# LogiGSM.net
KiCad netlist of a schematic drawn in EAGLE
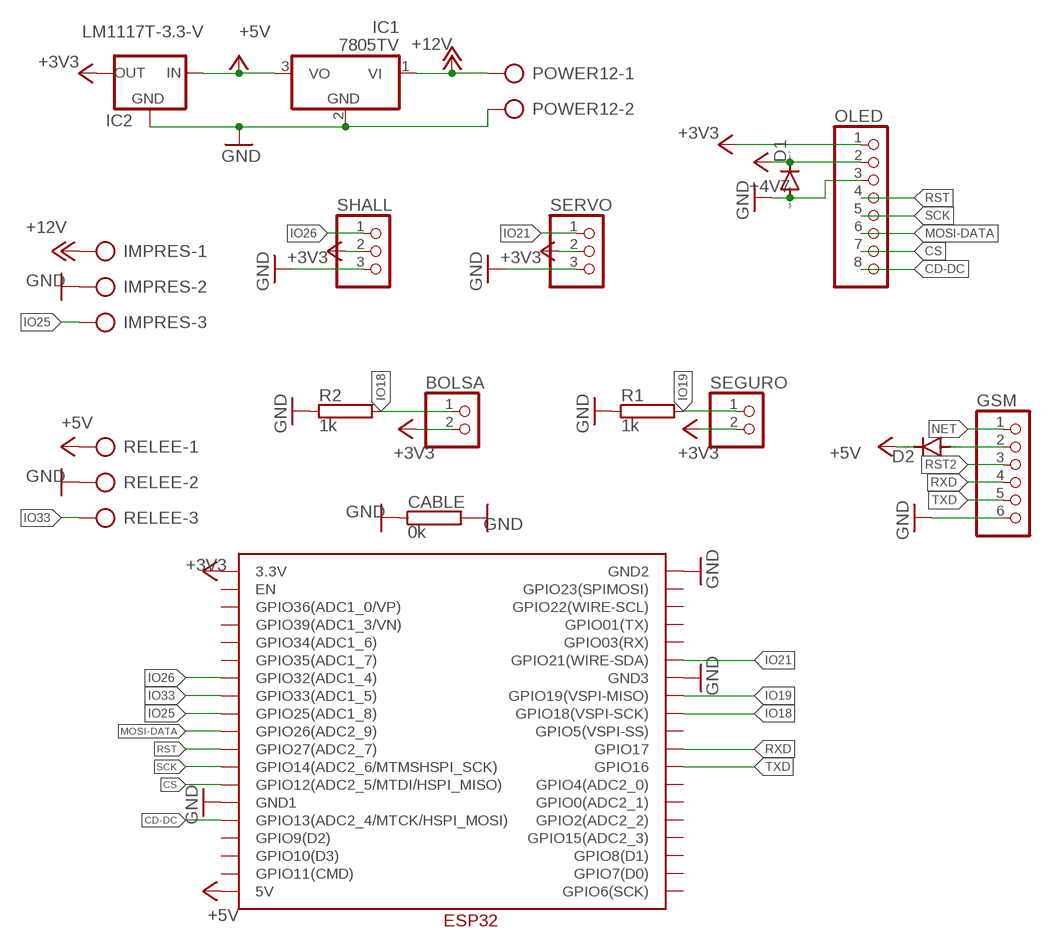
[diagram p0: schematic, sheet 1]

(export (version "E")
  (design (tool "Eeschema 10.0.6"))
  (components
    (comp (ref "BOLSA")
      (value "PINHD-1X2")
      (footprint "eagle-import:1X02")
      (libsource (lib "eagle-import") (part "PINHD-1X2"))
    )
    (comp (ref "CABLE")
      (value "0k")
      (footprint "eagle-import:RS1_2")
      (fields (field (name "MF") "OHMITE") (field (name "MPN") "RRS1K0E"))
      (libsource (lib "eagle-import") (part "RRS1/2"))
    )
    (comp (ref "D1")
      (value "DIODE-SOD81")
      (footprint "eagle-import:SOD81")
      (libsource (lib "eagle-import") (part "DIODE-SOD81"))
    )
    (comp (ref "D2")
      (value "DIODE-SOD81")
      (footprint "eagle-import:SOD81")
      (libsource (lib "eagle-import") (part "DIODE-SOD81"))
    )
    (comp (ref "GSM")
      (value "PINHD-1X6")
      (footprint "eagle-import:1X06")
      (libsource (lib "eagle-import") (part "PINHD-1X6"))
    )
    (comp (ref "IC1")
      (value "7805TV")
      (footprint "eagle-import:TO220V")
      (libsource (lib "eagle-import") (part "78TV05"))
    )
    (comp (ref "IC2")
      (value "LM1117T-3.3-V")
      (footprint "eagle-import:TO220V")
      (libsource (lib "eagle-import") (part "LM1117T--V3.3"))
    )
    (comp (ref "IMPRES")
      (value "AK500/3")
      (footprint "eagle-import:AK500_3")
      (libsource (lib "eagle-import") (part "AK500/3"))
    )
    (comp (ref "OLED")
      (value "PINHD-1X8")
      (footprint "eagle-import:1X08")
      (libsource (lib "eagle-import") (part "PINHD-1X8"))
    )
    (comp (ref "POWER12")
      (value "AK500/2")
      (footprint "eagle-import:AK500_2")
      (libsource (lib "eagle-import") (part "AK500/2"))
    )
    (comp (ref "R1")
      (value "1k")
      (footprint "eagle-import:RS1_8")
      (libsource (lib "eagle-import") (part "resistor-powerV2_RRS1/8"))
    )
    (comp (ref "R2")
      (value "1k")
      (footprint "eagle-import:RS1_8")
      (libsource (lib "eagle-import") (part "resistor-powerV2_RRS1/8"))
    )
    (comp (ref "RELEE")
      (value "AK500/3")
      (footprint "eagle-import:AK500_3")
      (libsource (lib "eagle-import") (part "AK500/3"))
    )
    (comp (ref "SEGURO")
      (value "PINHD-1X2")
      (footprint "eagle-import:1X02")
      (libsource (lib "eagle-import") (part "PINHD-1X2"))
    )
    (comp (ref "SERVO")
      (value "PINHD-1X3")
      (footprint "eagle-import:1X03")
      (libsource (lib "eagle-import") (part "PINHD-1X3"))
    )
    (comp (ref "SHALL")
      (value "PINHD-1X3")
      (footprint "eagle-import:1X03")
      (libsource (lib "eagle-import") (part "PINHD-1X3"))
    )
    (comp (ref "U$1")
      (value "ESP32WESP32W")
      (footprint "eagle-import:ESP32W")
      (libsource (lib "eagle-import") (part "ESP32WESP32W"))
    )
  )
  (nets
    (net (code "1") (name "+3V3") (class "Default")
      (node (ref "BOLSA") (pin "2") (pinfunction "2_2") (pintype "passive"))
      (node (ref "IC2") (pin "2") (pinfunction "OUT_2") (pintype "passive"))
      (node (ref "OLED") (pin "1") (pinfunction "1_1") (pintype "passive"))
      (node (ref "SEGURO") (pin "2") (pinfunction "2_2") (pintype "passive"))
      (node (ref "SERVO") (pin "2") (pinfunction "2_2") (pintype "passive"))
      (node (ref "SHALL") (pin "2") (pinfunction "2_2") (pintype "passive"))
      (node (ref "U$1") (pin "3.3V") (pinfunction "3.3V_3.3V") (pintype "bidirectional"))
    )
    (net (code "2") (name "+4V7") (class "Default")
      (node (ref "D1") (pin "C") (pinfunction "C_C") (pintype "passive"))
      (node (ref "D2") (pin "C") (pinfunction "C_C") (pintype "passive"))
      (node (ref "IC1") (pin "3") (pinfunction "VO_3") (pintype "passive"))
      (node (ref "IC2") (pin "3") (pinfunction "IN_3") (pintype "input"))
      (node (ref "OLED") (pin "2") (pinfunction "2_2") (pintype "passive"))
      (node (ref "RELEE") (pin "1") (pinfunction "KL_1") (pintype "passive"))
      (node (ref "U$1") (pin "5V") (pinfunction "5V_5V") (pintype "bidirectional"))
    )
    (net (code "3") (name "+12V") (class "Default")
      (node (ref "IC1") (pin "1") (pinfunction "VI_1") (pintype "input"))
      (node (ref "IMPRES") (pin "1") (pinfunction "KL_1") (pintype "passive"))
      (node (ref "POWER12") (pin "1") (pinfunction "KL_1") (pintype "passive"))
    )
    (net (code "4") (name "CD-DC") (class "Default")
      (node (ref "OLED") (pin "8") (pinfunction "8_8") (pintype "passive"))
      (node (ref "U$1") (pin "GPIO13") (pinfunction "GPIO13(ADC2_4/MTCK/HSPI_MOSI)_GPIO13") (pintype "bidirectional"))
    )
    (net (code "5") (name "CS") (class "Default")
      (node (ref "OLED") (pin "7") (pinfunction "7_7") (pintype "passive"))
      (node (ref "U$1") (pin "GPIO12") (pinfunction "GPIO12(ADC2_5/MTDI/HSPI_MISO)_GPIO12") (pintype "bidirectional"))
    )
    (net (code "6") (name "GND") (class "Default")
      (node (ref "CABLE") (pin "1") (pinfunction "1_1") (pintype "passive"))
      (node (ref "CABLE") (pin "2") (pinfunction "2_2") (pintype "passive"))
      (node (ref "D1") (pin "A") (pinfunction "A_A") (pintype "passive"))
      (node (ref "GSM") (pin "6") (pinfunction "6_6") (pintype "passive"))
      (node (ref "IC1") (pin "2") (pinfunction "GND_2") (pintype "passive"))
      (node (ref "IC2") (pin "1") (pinfunction "GND_1") (pintype "input"))
      (node (ref "IMPRES") (pin "2") (pinfunction "KL_2") (pintype "passive"))
      (node (ref "OLED") (pin "3") (pinfunction "3_3") (pintype "passive"))
      (node (ref "POWER12") (pin "2") (pinfunction "KL_2") (pintype "passive"))
      (node (ref "R1") (pin "1") (pinfunction "1_1") (pintype "passive"))
      (node (ref "R2") (pin "1") (pinfunction "1_1") (pintype "passive"))
      (node (ref "RELEE") (pin "2") (pinfunction "KL_2") (pintype "passive"))
      (node (ref "SERVO") (pin "3") (pinfunction "3_3") (pintype "passive"))
      (node (ref "SHALL") (pin "3") (pinfunction "3_3") (pintype "passive"))
      (node (ref "U$1") (pin "GND1") (pinfunction "GND1_GND1") (pintype "bidirectional"))
      (node (ref "U$1") (pin "GND2") (pinfunction "GND2_GND2") (pintype "bidirectional"))
      (node (ref "U$1") (pin "GND3") (pinfunction "GND3_GND3") (pintype "bidirectional"))
    )
    (net (code "7") (name "IO18") (class "Default")
      (node (ref "BOLSA") (pin "1") (pinfunction "1_1") (pintype "passive"))
      (node (ref "R2") (pin "2") (pinfunction "2_2") (pintype "passive"))
      (node (ref "U$1") (pin "GPIO18") (pinfunction "GPIO18(VSPI-SCK)_GPIO18") (pintype "bidirectional"))
    )
    (net (code "8") (name "IO19") (class "Default")
      (node (ref "R1") (pin "2") (pinfunction "2_2") (pintype "passive"))
      (node (ref "SEGURO") (pin "1") (pinfunction "1_1") (pintype "passive"))
      (node (ref "U$1") (pin "GPIO19") (pinfunction "GPIO19(VSPI-MISO)_GPIO19") (pintype "bidirectional"))
    )
    (net (code "9") (name "IO21") (class "Default")
      (node (ref "SERVO") (pin "1") (pinfunction "1_1") (pintype "passive"))
      (node (ref "U$1") (pin "GPIO21") (pinfunction "GPIO21(WIRE-SDA)_GPIO21") (pintype "bidirectional"))
    )
    (net (code "10") (name "IO25") (class "Default")
      (node (ref "IMPRES") (pin "3") (pinfunction "KL_3") (pintype "passive"))
      (node (ref "U$1") (pin "GPIO25") (pinfunction "GPIO25(ADC1_8)_GPIO25") (pintype "bidirectional"))
    )
    (net (code "11") (name "IO26") (class "Default")
      (node (ref "SHALL") (pin "1") (pinfunction "1_1") (pintype "passive"))
      (node (ref "U$1") (pin "GPIO32") (pinfunction "GPIO32(ADC1_4)_GPIO32") (pintype "bidirectional"))
    )
    (net (code "12") (name "IO33") (class "Default")
      (node (ref "RELEE") (pin "3") (pinfunction "KL_3") (pintype "passive"))
      (node (ref "U$1") (pin "GPIO33") (pinfunction "GPIO33(ADC1_5)_GPIO33") (pintype "bidirectional"))
    )
    (net (code "13") (name "MOSI-DATA") (class "Default")
      (node (ref "OLED") (pin "6") (pinfunction "6_6") (pintype "passive"))
      (node (ref "U$1") (pin "GPIO26") (pinfunction "GPIO26(ADC2_9)_GPIO26") (pintype "bidirectional"))
    )
    (net (code "14") (name "NET") (class "Default")
      (node (ref "GSM") (pin "1") (pinfunction "1_1") (pintype "passive"))
    )
    (net (code "15") (name "Net-(D2-PadA)") (class "Default")
      (node (ref "D2") (pin "A") (pinfunction "A_A") (pintype "passive"))
      (node (ref "GSM") (pin "2") (pinfunction "2_2") (pintype "passive"))
    )
    (net (code "16") (name "RST") (class "Default")
      (node (ref "OLED") (pin "4") (pinfunction "4_4") (pintype "passive"))
      (node (ref "U$1") (pin "GPIO27") (pinfunction "GPIO27(ADC2_7)_GPIO27") (pintype "bidirectional"))
    )
    (net (code "17") (name "RST2") (class "Default")
      (node (ref "GSM") (pin "3") (pinfunction "3_3") (pintype "passive"))
    )
    (net (code "18") (name "RXD") (class "Default")
      (node (ref "GSM") (pin "4") (pinfunction "4_4") (pintype "passive"))
      (node (ref "U$1") (pin "GPIO17") (pinfunction "GPIO17_GPIO17") (pintype "bidirectional"))
    )
    (net (code "19") (name "SCK") (class "Default")
      (node (ref "OLED") (pin "5") (pinfunction "5_5") (pintype "passive"))
      (node (ref "U$1") (pin "GPIO14") (pinfunction "GPIO14(ADC2_6/MTMSHSPI_SCK)_GPIO14") (pintype "bidirectional"))
    )
    (net (code "20") (name "TXD") (class "Default")
      (node (ref "GSM") (pin "5") (pinfunction "5_5") (pintype "passive"))
      (node (ref "U$1") (pin "GPIO16") (pinfunction "GPIO16_GPIO16") (pintype "bidirectional"))
    )
    (net (code "21") (name "unconnected-(U$1-GPIO0(ADC2_1)-PadGPIO0)") (class "Default")
      (node (ref "U$1") (pin "GPIO0") (pinfunction "GPIO0(ADC2_1)_GPIO0") (pintype "bidirectional"))
    )
    (net (code "22") (name "unconnected-(U$1-GPIO01(TX)-PadTX)") (class "Default")
      (node (ref "U$1") (pin "TX") (pinfunction "GPIO01(TX)_TX") (pintype "bidirectional"))
    )
    (net (code "23") (name "unconnected-(U$1-GPIO2(ADC2_2)-PadGPIO2)") (class "Default")
      (node (ref "U$1") (pin "GPIO2") (pinfunction "GPIO2(ADC2_2)_GPIO2") (pintype "bidirectional"))
    )
    (net (code "24") (name "unconnected-(U$1-GPIO03(RX)-PadRX)") (class "Default")
      (node (ref "U$1") (pin "RX") (pinfunction "GPIO03(RX)_RX") (pintype "bidirectional"))
    )
    (net (code "25") (name "unconnected-(U$1-GPIO4(ADC2_0)-PadGPIO4)") (class "Default")
      (node (ref "U$1") (pin "GPIO4") (pinfunction "GPIO4(ADC2_0)_GPIO4") (pintype "bidirectional"))
    )
    (net (code "26") (name "unconnected-(U$1-GPIO5(VSPI-SS)-PadGPIO5)") (class "Default")
      (node (ref "U$1") (pin "GPIO5") (pinfunction "GPIO5(VSPI-SS)_GPIO5") (pintype "bidirectional"))
    )
    (net (code "27") (name "unconnected-(U$1-GPIO6(SCK)-PadCLK)") (class "Default")
      (node (ref "U$1") (pin "CLK") (pinfunction "GPIO6(SCK)_CLK") (pintype "bidirectional"))
    )
    (net (code "28") (name "unconnected-(U$1-GPIO7(D0)-PadSDO)") (class "Default")
      (node (ref "U$1") (pin "SDO") (pinfunction "GPIO7(D0)_SDO") (pintype "bidirectional"))
    )
    (net (code "29") (name "unconnected-(U$1-GPIO8(D1)-PadSDI)") (class "Default")
      (node (ref "U$1") (pin "SDI") (pinfunction "GPIO8(D1)_SDI") (pintype "bidirectional"))
    )
    (net (code "30") (name "unconnected-(U$1-GPIO9(D2)-PadD2)") (class "Default")
      (node (ref "U$1") (pin "D2") (pinfunction "GPIO9(D2)_D2") (pintype "bidirectional"))
    )
    (net (code "31") (name "unconnected-(U$1-GPIO10(D3)-PadD3)") (class "Default")
      (node (ref "U$1") (pin "D3") (pinfunction "GPIO10(D3)_D3") (pintype "bidirectional"))
    )
    (net (code "32") (name "unconnected-(U$1-GPIO11(CMD)-PadCMD)") (class "Default")
      (node (ref "U$1") (pin "CMD") (pinfunction "GPIO11(CMD)_CMD") (pintype "bidirectional"))
    )
    (net (code "33") (name "unconnected-(U$1-GPIO15(ADC2_3)-PadGPIO15)") (class "Default")
      (node (ref "U$1") (pin "GPIO15") (pinfunction "GPIO15(ADC2_3)_GPIO15") (pintype "bidirectional"))
    )
    (net (code "34") (name "unconnected-(U$1-GPIO22(WIRE-SCL)-PadGPIO22)") (class "Default")
      (node (ref "U$1") (pin "GPIO22") (pinfunction "GPIO22(WIRE-SCL)_GPIO22") (pintype "bidirectional"))
    )
    (net (code "35") (name "unconnected-(U$1-GPIO23(SPIMOSI)-PadGPIO23)") (class "Default")
      (node (ref "U$1") (pin "GPIO23") (pinfunction "GPIO23(SPIMOSI)_GPIO23") (pintype "bidirectional"))
    )
    (net (code "36") (name "unconnected-(U$1-GPIO34(ADC1_6)-PadGPIO34)") (class "Default")
      (node (ref "U$1") (pin "GPIO34") (pinfunction "GPIO34(ADC1_6)_GPIO34") (pintype "bidirectional"))
    )
    (net (code "37") (name "unconnected-(U$1-GPIO35(ADC1_7)-PadGPIO35)") (class "Default")
      (node (ref "U$1") (pin "GPIO35") (pinfunction "GPIO35(ADC1_7)_GPIO35") (pintype "bidirectional"))
    )
    (net (code "38") (name "unconnected-(U$1-GPIO36(ADC1_0{slash}VP)-PadVP)") (class "Default")
      (node (ref "U$1") (pin "VP") (pinfunction "GPIO36(ADC1_0/VP)_VP") (pintype "bidirectional"))
    )
    (net (code "39") (name "unconnected-(U$1-GPIO39(ADC1_3{slash}VN)-PadVN)") (class "Default")
      (node (ref "U$1") (pin "VN") (pinfunction "GPIO39(ADC1_3/VN)_VN") (pintype "bidirectional"))
    )
    (net (code "40") (name "unconnected-(U$1-PadEN)") (class "Default")
      (node (ref "U$1") (pin "EN") (pinfunction "EN_EN") (pintype "bidirectional"))
    )
  )
)
